# proto1.net
KiCad netlist of a schematic drawn in EAGLE
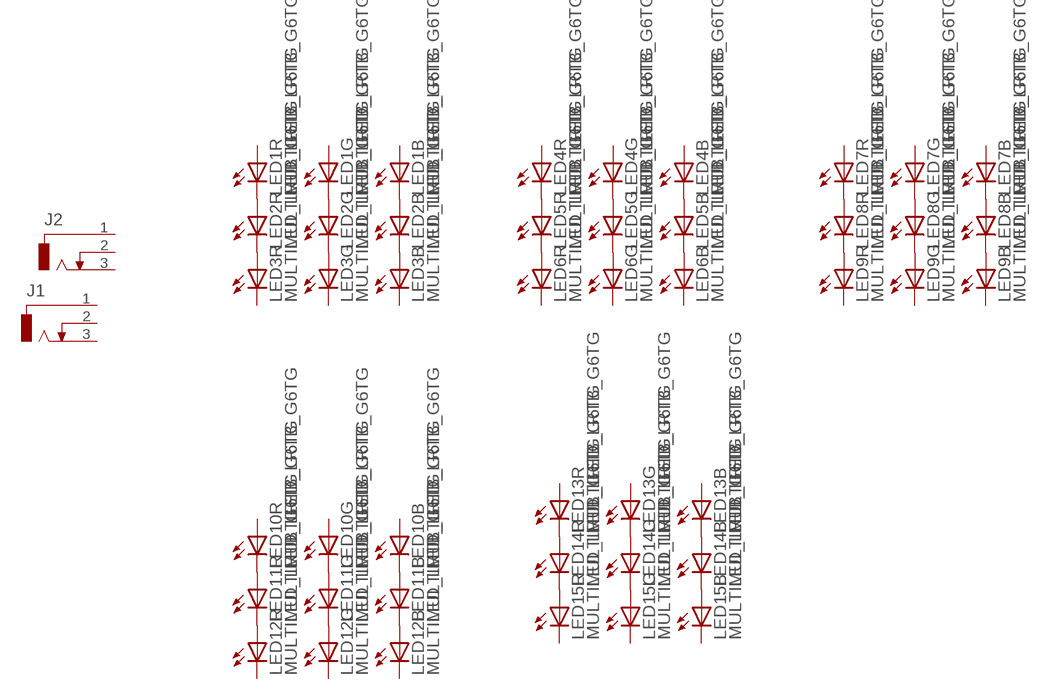
[diagram p0: schematic, sheet 1]

(export (version "E")
  (design (tool "Eeschema 10.0.6"))
  (components
    (comp (ref "J1")
      (value "DCJ0303")
      (footprint "eagle-import:DCJ0303")
      (fields (field (name "OC_FARNELL") "unknown") (field (name "OC_NEWARK") "unknown"))
      (libsource (lib "eagle-import") (part "DCJ0303"))
    )
    (comp (ref "J2")
      (value "DCJ0303")
      (footprint "eagle-import:DCJ0303")
      (libsource (lib "eagle-import") (part "DCJ0303"))
    )
    (comp (ref "LED1")
      (value "MULTILED_LRTB_G6TG")
      (footprint "eagle-import:P-LCC-6_TOPLED")
      (libsource (lib "eagle-import") (part "MULTILED_LRTB_G6TG"))
    )
    (comp (ref "LED2")
      (value "MULTILED_LRTB_G6TG")
      (footprint "eagle-import:P-LCC-6_TOPLED")
      (libsource (lib "eagle-import") (part "MULTILED_LRTB_G6TG"))
    )
    (comp (ref "LED3")
      (value "MULTILED_LRTB_G6TG")
      (footprint "eagle-import:P-LCC-6_TOPLED")
      (libsource (lib "eagle-import") (part "MULTILED_LRTB_G6TG"))
    )
    (comp (ref "LED4")
      (value "MULTILED_LRTB_G6TG")
      (footprint "eagle-import:P-LCC-6_TOPLED")
      (libsource (lib "eagle-import") (part "MULTILED_LRTB_G6TG"))
    )
    (comp (ref "LED5")
      (value "MULTILED_LRTB_G6TG")
      (footprint "eagle-import:P-LCC-6_TOPLED")
      (libsource (lib "eagle-import") (part "MULTILED_LRTB_G6TG"))
    )
    (comp (ref "LED6")
      (value "MULTILED_LRTB_G6TG")
      (footprint "eagle-import:P-LCC-6_TOPLED")
      (libsource (lib "eagle-import") (part "MULTILED_LRTB_G6TG"))
    )
    (comp (ref "LED7")
      (value "MULTILED_LRTB_G6TG")
      (footprint "eagle-import:P-LCC-6_TOPLED")
      (libsource (lib "eagle-import") (part "MULTILED_LRTB_G6TG"))
    )
    (comp (ref "LED8")
      (value "MULTILED_LRTB_G6TG")
      (footprint "eagle-import:P-LCC-6_TOPLED")
      (libsource (lib "eagle-import") (part "MULTILED_LRTB_G6TG"))
    )
    (comp (ref "LED9")
      (value "MULTILED_LRTB_G6TG")
      (footprint "eagle-import:P-LCC-6_TOPLED")
      (libsource (lib "eagle-import") (part "MULTILED_LRTB_G6TG"))
    )
    (comp (ref "LED10")
      (value "MULTILED_LRTB_G6TG")
      (footprint "eagle-import:P-LCC-6_TOPLED")
      (libsource (lib "eagle-import") (part "MULTILED_LRTB_G6TG"))
    )
    (comp (ref "LED11")
      (value "MULTILED_LRTB_G6TG")
      (footprint "eagle-import:P-LCC-6_TOPLED")
      (libsource (lib "eagle-import") (part "MULTILED_LRTB_G6TG"))
    )
    (comp (ref "LED12")
      (value "MULTILED_LRTB_G6TG")
      (footprint "eagle-import:P-LCC-6_TOPLED")
      (libsource (lib "eagle-import") (part "MULTILED_LRTB_G6TG"))
    )
    (comp (ref "LED13")
      (value "MULTILED_LRTB_G6TG")
      (footprint "eagle-import:P-LCC-6_TOPLED")
      (libsource (lib "eagle-import") (part "MULTILED_LRTB_G6TG"))
    )
    (comp (ref "LED14")
      (value "MULTILED_LRTB_G6TG")
      (footprint "eagle-import:P-LCC-6_TOPLED")
      (libsource (lib "eagle-import") (part "MULTILED_LRTB_G6TG"))
    )
    (comp (ref "LED15")
      (value "MULTILED_LRTB_G6TG")
      (footprint "eagle-import:P-LCC-6_TOPLED")
      (libsource (lib "eagle-import") (part "MULTILED_LRTB_G6TG"))
    )
  )
  (nets
    (net (code "1") (name "Net-(LED1A-C)") (class "Default")
      (node (ref "LED1") (pin "C3") (pinfunction "C_C3") (pintype "passive"))
      (node (ref "LED2") (pin "A3") (pinfunction "A_A3") (pintype "passive"))
    )
    (net (code "2") (name "Net-(LED1B-C)") (class "Default")
      (node (ref "LED1") (pin "C2") (pinfunction "C_C2") (pintype "passive"))
      (node (ref "LED2") (pin "A2") (pinfunction "A_A2") (pintype "passive"))
    )
    (net (code "3") (name "Net-(LED1C-C)") (class "Default")
      (node (ref "LED1") (pin "C1") (pinfunction "C_C1") (pintype "passive"))
      (node (ref "LED2") (pin "A1") (pinfunction "A_A1") (pintype "passive"))
    )
    (net (code "4") (name "Net-(LED2A-C)") (class "Default")
      (node (ref "LED2") (pin "C3") (pinfunction "C_C3") (pintype "passive"))
      (node (ref "LED3") (pin "A3") (pinfunction "A_A3") (pintype "passive"))
    )
    (net (code "5") (name "Net-(LED2B-C)") (class "Default")
      (node (ref "LED2") (pin "C2") (pinfunction "C_C2") (pintype "passive"))
      (node (ref "LED3") (pin "A2") (pinfunction "A_A2") (pintype "passive"))
    )
    (net (code "6") (name "Net-(LED2C-C)") (class "Default")
      (node (ref "LED2") (pin "C1") (pinfunction "C_C1") (pintype "passive"))
      (node (ref "LED3") (pin "A1") (pinfunction "A_A1") (pintype "passive"))
    )
    (net (code "7") (name "Net-(LED4A-C)") (class "Default")
      (node (ref "LED4") (pin "C3") (pinfunction "C_C3") (pintype "passive"))
      (node (ref "LED5") (pin "A3") (pinfunction "A_A3") (pintype "passive"))
    )
    (net (code "8") (name "Net-(LED4B-C)") (class "Default")
      (node (ref "LED4") (pin "C2") (pinfunction "C_C2") (pintype "passive"))
      (node (ref "LED5") (pin "A2") (pinfunction "A_A2") (pintype "passive"))
    )
    (net (code "9") (name "Net-(LED4C-C)") (class "Default")
      (node (ref "LED4") (pin "C1") (pinfunction "C_C1") (pintype "passive"))
      (node (ref "LED5") (pin "A1") (pinfunction "A_A1") (pintype "passive"))
    )
    (net (code "10") (name "Net-(LED5A-C)") (class "Default")
      (node (ref "LED5") (pin "C3") (pinfunction "C_C3") (pintype "passive"))
      (node (ref "LED6") (pin "A3") (pinfunction "A_A3") (pintype "passive"))
    )
    (net (code "11") (name "Net-(LED5B-C)") (class "Default")
      (node (ref "LED5") (pin "C2") (pinfunction "C_C2") (pintype "passive"))
      (node (ref "LED6") (pin "A2") (pinfunction "A_A2") (pintype "passive"))
    )
    (net (code "12") (name "Net-(LED5C-C)") (class "Default")
      (node (ref "LED5") (pin "C1") (pinfunction "C_C1") (pintype "passive"))
      (node (ref "LED6") (pin "A1") (pinfunction "A_A1") (pintype "passive"))
    )
    (net (code "13") (name "Net-(LED7A-C)") (class "Default")
      (node (ref "LED7") (pin "C3") (pinfunction "C_C3") (pintype "passive"))
      (node (ref "LED8") (pin "A3") (pinfunction "A_A3") (pintype "passive"))
    )
    (net (code "14") (name "Net-(LED7B-C)") (class "Default")
      (node (ref "LED7") (pin "C2") (pinfunction "C_C2") (pintype "passive"))
      (node (ref "LED8") (pin "A2") (pinfunction "A_A2") (pintype "passive"))
    )
    (net (code "15") (name "Net-(LED7C-C)") (class "Default")
      (node (ref "LED7") (pin "C1") (pinfunction "C_C1") (pintype "passive"))
      (node (ref "LED8") (pin "A1") (pinfunction "A_A1") (pintype "passive"))
    )
    (net (code "16") (name "Net-(LED8A-C)") (class "Default")
      (node (ref "LED8") (pin "C3") (pinfunction "C_C3") (pintype "passive"))
      (node (ref "LED9") (pin "A3") (pinfunction "A_A3") (pintype "passive"))
    )
    (net (code "17") (name "Net-(LED8B-C)") (class "Default")
      (node (ref "LED8") (pin "C2") (pinfunction "C_C2") (pintype "passive"))
      (node (ref "LED9") (pin "A2") (pinfunction "A_A2") (pintype "passive"))
    )
    (net (code "18") (name "Net-(LED8C-C)") (class "Default")
      (node (ref "LED8") (pin "C1") (pinfunction "C_C1") (pintype "passive"))
      (node (ref "LED9") (pin "A1") (pinfunction "A_A1") (pintype "passive"))
    )
    (net (code "19") (name "Net-(LED10A-C)") (class "Default")
      (node (ref "LED10") (pin "C3") (pinfunction "C_C3") (pintype "passive"))
      (node (ref "LED11") (pin "A3") (pinfunction "A_A3") (pintype "passive"))
    )
    (net (code "20") (name "Net-(LED10B-C)") (class "Default")
      (node (ref "LED10") (pin "C2") (pinfunction "C_C2") (pintype "passive"))
      (node (ref "LED11") (pin "A2") (pinfunction "A_A2") (pintype "passive"))
    )
    (net (code "21") (name "Net-(LED10C-C)") (class "Default")
      (node (ref "LED10") (pin "C1") (pinfunction "C_C1") (pintype "passive"))
      (node (ref "LED11") (pin "A1") (pinfunction "A_A1") (pintype "passive"))
    )
    (net (code "22") (name "Net-(LED11A-C)") (class "Default")
      (node (ref "LED11") (pin "C3") (pinfunction "C_C3") (pintype "passive"))
      (node (ref "LED12") (pin "A3") (pinfunction "A_A3") (pintype "passive"))
    )
    (net (code "23") (name "Net-(LED11B-C)") (class "Default")
      (node (ref "LED11") (pin "C2") (pinfunction "C_C2") (pintype "passive"))
      (node (ref "LED12") (pin "A2") (pinfunction "A_A2") (pintype "passive"))
    )
    (net (code "24") (name "Net-(LED11C-C)") (class "Default")
      (node (ref "LED11") (pin "C1") (pinfunction "C_C1") (pintype "passive"))
      (node (ref "LED12") (pin "A1") (pinfunction "A_A1") (pintype "passive"))
    )
    (net (code "25") (name "Net-(LED13A-C)") (class "Default")
      (node (ref "LED13") (pin "C3") (pinfunction "C_C3") (pintype "passive"))
      (node (ref "LED14") (pin "A3") (pinfunction "A_A3") (pintype "passive"))
    )
    (net (code "26") (name "Net-(LED13B-C)") (class "Default")
      (node (ref "LED13") (pin "C2") (pinfunction "C_C2") (pintype "passive"))
      (node (ref "LED14") (pin "A2") (pinfunction "A_A2") (pintype "passive"))
    )
    (net (code "27") (name "Net-(LED13C-C)") (class "Default")
      (node (ref "LED13") (pin "C1") (pinfunction "C_C1") (pintype "passive"))
      (node (ref "LED14") (pin "A1") (pinfunction "A_A1") (pintype "passive"))
    )
    (net (code "28") (name "Net-(LED14A-C)") (class "Default")
      (node (ref "LED14") (pin "C3") (pinfunction "C_C3") (pintype "passive"))
      (node (ref "LED15") (pin "A3") (pinfunction "A_A3") (pintype "passive"))
    )
    (net (code "29") (name "Net-(LED14B-C)") (class "Default")
      (node (ref "LED14") (pin "C2") (pinfunction "C_C2") (pintype "passive"))
      (node (ref "LED15") (pin "A2") (pinfunction "A_A2") (pintype "passive"))
    )
    (net (code "30") (name "Net-(LED14C-C)") (class "Default")
      (node (ref "LED14") (pin "C1") (pinfunction "C_C1") (pintype "passive"))
      (node (ref "LED15") (pin "A1") (pinfunction "A_A1") (pintype "passive"))
    )
    (net (code "31") (name "unconnected-(J1-Pad1)") (class "Default")
      (node (ref "J1") (pin "1") (pinfunction "1_1") (pintype "passive"))
    )
    (net (code "32") (name "unconnected-(J1-Pad2)") (class "Default")
      (node (ref "J1") (pin "2") (pinfunction "2_2") (pintype "passive"))
    )
    (net (code "33") (name "unconnected-(J1-Pad3)") (class "Default")
      (node (ref "J1") (pin "3") (pinfunction "3_3") (pintype "passive"))
    )
    (net (code "34") (name "unconnected-(J2-Pad1)") (class "Default")
      (node (ref "J2") (pin "1") (pinfunction "1_1") (pintype "passive"))
    )
    (net (code "35") (name "unconnected-(J2-Pad2)") (class "Default")
      (node (ref "J2") (pin "2") (pinfunction "2_2") (pintype "passive"))
    )
    (net (code "36") (name "unconnected-(J2-Pad3)") (class "Default")
      (node (ref "J2") (pin "3") (pinfunction "3_3") (pintype "passive"))
    )
    (net (code "37") (name "unconnected-(LED1A-A-PadA3)") (class "Default")
      (node (ref "LED1") (pin "A3") (pinfunction "A_A3") (pintype "passive"))
    )
    (net (code "38") (name "unconnected-(LED1B-A-PadA2)") (class "Default")
      (node (ref "LED1") (pin "A2") (pinfunction "A_A2") (pintype "passive"))
    )
    (net (code "39") (name "unconnected-(LED1C-A-PadA1)") (class "Default")
      (node (ref "LED1") (pin "A1") (pinfunction "A_A1") (pintype "passive"))
    )
    (net (code "40") (name "unconnected-(LED3A-C-PadC3)") (class "Default")
      (node (ref "LED3") (pin "C3") (pinfunction "C_C3") (pintype "passive"))
    )
    (net (code "41") (name "unconnected-(LED3B-C-PadC2)") (class "Default")
      (node (ref "LED3") (pin "C2") (pinfunction "C_C2") (pintype "passive"))
    )
    (net (code "42") (name "unconnected-(LED3C-C-PadC1)") (class "Default")
      (node (ref "LED3") (pin "C1") (pinfunction "C_C1") (pintype "passive"))
    )
    (net (code "43") (name "unconnected-(LED4A-A-PadA3)") (class "Default")
      (node (ref "LED4") (pin "A3") (pinfunction "A_A3") (pintype "passive"))
    )
    (net (code "44") (name "unconnected-(LED4B-A-PadA2)") (class "Default")
      (node (ref "LED4") (pin "A2") (pinfunction "A_A2") (pintype "passive"))
    )
    (net (code "45") (name "unconnected-(LED4C-A-PadA1)") (class "Default")
      (node (ref "LED4") (pin "A1") (pinfunction "A_A1") (pintype "passive"))
    )
    (net (code "46") (name "unconnected-(LED6A-C-PadC3)") (class "Default")
      (node (ref "LED6") (pin "C3") (pinfunction "C_C3") (pintype "passive"))
    )
    (net (code "47") (name "unconnected-(LED6B-C-PadC2)") (class "Default")
      (node (ref "LED6") (pin "C2") (pinfunction "C_C2") (pintype "passive"))
    )
    (net (code "48") (name "unconnected-(LED6C-C-PadC1)") (class "Default")
      (node (ref "LED6") (pin "C1") (pinfunction "C_C1") (pintype "passive"))
    )
    (net (code "49") (name "unconnected-(LED7A-A-PadA3)") (class "Default")
      (node (ref "LED7") (pin "A3") (pinfunction "A_A3") (pintype "passive"))
    )
    (net (code "50") (name "unconnected-(LED7B-A-PadA2)") (class "Default")
      (node (ref "LED7") (pin "A2") (pinfunction "A_A2") (pintype "passive"))
    )
    (net (code "51") (name "unconnected-(LED7C-A-PadA1)") (class "Default")
      (node (ref "LED7") (pin "A1") (pinfunction "A_A1") (pintype "passive"))
    )
    (net (code "52") (name "unconnected-(LED9A-C-PadC3)") (class "Default")
      (node (ref "LED9") (pin "C3") (pinfunction "C_C3") (pintype "passive"))
    )
    (net (code "53") (name "unconnected-(LED9B-C-PadC2)") (class "Default")
      (node (ref "LED9") (pin "C2") (pinfunction "C_C2") (pintype "passive"))
    )
    (net (code "54") (name "unconnected-(LED9C-C-PadC1)") (class "Default")
      (node (ref "LED9") (pin "C1") (pinfunction "C_C1") (pintype "passive"))
    )
    (net (code "55") (name "unconnected-(LED10A-A-PadA3)") (class "Default")
      (node (ref "LED10") (pin "A3") (pinfunction "A_A3") (pintype "passive"))
    )
    (net (code "56") (name "unconnected-(LED10B-A-PadA2)") (class "Default")
      (node (ref "LED10") (pin "A2") (pinfunction "A_A2") (pintype "passive"))
    )
    (net (code "57") (name "unconnected-(LED10C-A-PadA1)") (class "Default")
      (node (ref "LED10") (pin "A1") (pinfunction "A_A1") (pintype "passive"))
    )
    (net (code "58") (name "unconnected-(LED12A-C-PadC3)") (class "Default")
      (node (ref "LED12") (pin "C3") (pinfunction "C_C3") (pintype "passive"))
    )
    (net (code "59") (name "unconnected-(LED12B-C-PadC2)") (class "Default")
      (node (ref "LED12") (pin "C2") (pinfunction "C_C2") (pintype "passive"))
    )
    (net (code "60") (name "unconnected-(LED12C-C-PadC1)") (class "Default")
      (node (ref "LED12") (pin "C1") (pinfunction "C_C1") (pintype "passive"))
    )
    (net (code "61") (name "unconnected-(LED13A-A-PadA3)") (class "Default")
      (node (ref "LED13") (pin "A3") (pinfunction "A_A3") (pintype "passive"))
    )
    (net (code "62") (name "unconnected-(LED13B-A-PadA2)") (class "Default")
      (node (ref "LED13") (pin "A2") (pinfunction "A_A2") (pintype "passive"))
    )
    (net (code "63") (name "unconnected-(LED13C-A-PadA1)") (class "Default")
      (node (ref "LED13") (pin "A1") (pinfunction "A_A1") (pintype "passive"))
    )
    (net (code "64") (name "unconnected-(LED15A-C-PadC3)") (class "Default")
      (node (ref "LED15") (pin "C3") (pinfunction "C_C3") (pintype "passive"))
    )
    (net (code "65") (name "unconnected-(LED15B-C-PadC2)") (class "Default")
      (node (ref "LED15") (pin "C2") (pinfunction "C_C2") (pintype "passive"))
    )
    (net (code "66") (name "unconnected-(LED15C-C-PadC1)") (class "Default")
      (node (ref "LED15") (pin "C1") (pinfunction "C_C1") (pintype "passive"))
    )
  )
)
